# tx35.net
KiCad netlist of a schematic drawn in EAGLE
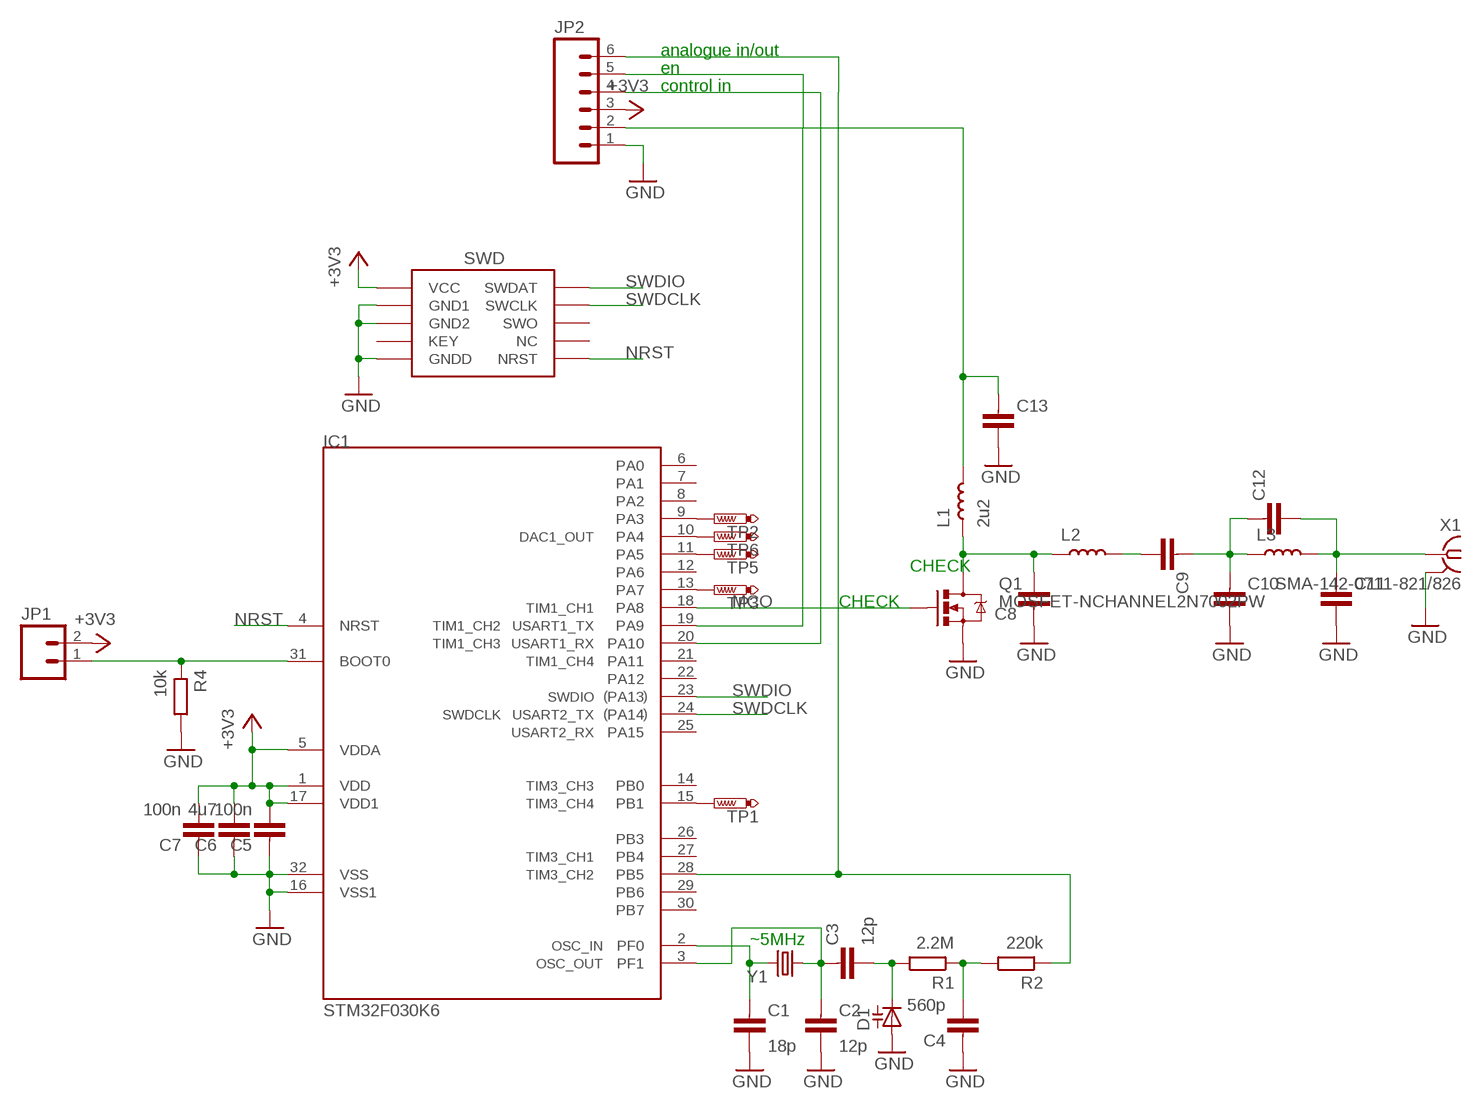
[diagram p0: schematic, sheet 1]

(export (version "E")
  (design (tool "Eeschema 10.0.6"))
  (components
    (comp (ref "C1")
      (value "18p")
      (footprint "eagle-import:C0603-N")
      (libsource (lib "eagle-import") (part "CAPACITOR0603-N"))
    )
    (comp (ref "C2")
      (value "12p")
      (footprint "eagle-import:C0603-N")
      (libsource (lib "eagle-import") (part "CAPACITOR0603-N"))
    )
    (comp (ref "C3")
      (value "12p")
      (footprint "eagle-import:C0603-N")
      (libsource (lib "eagle-import") (part "CAPACITOR0603-N"))
    )
    (comp (ref "C4")
      (value "560p")
      (footprint "eagle-import:C0603-N")
      (libsource (lib "eagle-import") (part "CAPACITOR0603-N"))
    )
    (comp (ref "C5")
      (value "100n")
      (footprint "eagle-import:C0603-N")
      (libsource (lib "eagle-import") (part "CAPACITOR0603-N"))
    )
    (comp (ref "C6")
      (value "4u7")
      (footprint "eagle-import:C0603-N")
      (libsource (lib "eagle-import") (part "CAPACITOR0603-N"))
    )
    (comp (ref "C7")
      (value "100n")
      (footprint "eagle-import:C0603-N")
      (libsource (lib "eagle-import") (part "CAPACITOR0603-N"))
    )
    (comp (ref "C8")
      (value "CAPACITOR0603-N")
      (footprint "eagle-import:C0603-N")
      (libsource (lib "eagle-import") (part "CAPACITOR0603-N"))
    )
    (comp (ref "C9")
      (value "CAPACITOR0603-N")
      (footprint "eagle-import:C0603-N")
      (libsource (lib "eagle-import") (part "CAPACITOR0603-N"))
    )
    (comp (ref "C10")
      (value "CAPACITOR0603-N")
      (footprint "eagle-import:C0603-N")
      (libsource (lib "eagle-import") (part "CAPACITOR0603-N"))
    )
    (comp (ref "C11")
      (value "CAPACITOR0603-N")
      (footprint "eagle-import:C0603-N")
      (libsource (lib "eagle-import") (part "CAPACITOR0603-N"))
    )
    (comp (ref "C12")
      (value "CAPACITOR0603-N")
      (footprint "eagle-import:C0603-N")
      (libsource (lib "eagle-import") (part "CAPACITOR0603-N"))
    )
    (comp (ref "C13")
      (value "CAPACITOR0805-N")
      (footprint "eagle-import:C0805-N")
      (libsource (lib "eagle-import") (part "CAPACITOR0805-N"))
    )
    (comp (ref "D1")
      (value "DIODE_CAPACITANCE-SOD523")
      (footprint "eagle-import:SOD523")
      (libsource (lib "eagle-import") (part "DIODE_CAPACITANCE-SOD523"))
    )
    (comp (ref "IC1")
      (value "STM32F030K6")
      (footprint "eagle-import:TQFP32-08")
      (libsource (lib "eagle-import") (part "STM32F0-32"))
    )
    (comp (ref "J1")
      (value "SWD_SHROUD")
      (footprint "eagle-import:SWD_PTH_SHROUD")
      (libsource (lib "eagle-import") (part "SWD_SHROUD"))
    )
    (comp (ref "JP1")
      (value "M02PTH")
      (footprint "eagle-import:1X02")
      (libsource (lib "eagle-import") (part "M02PTH"))
    )
    (comp (ref "JP2")
      (value "M06SILK_FEMALE_PTH")
      (footprint "eagle-import:1X06")
      (libsource (lib "eagle-import") (part "M06SILK_FEMALE_PTH"))
    )
    (comp (ref "L1")
      (value "2u2")
      (footprint "eagle-import:L0603-N")
      (libsource (lib "eagle-import") (part "INDUCTOR0603-N"))
    )
    (comp (ref "L2")
      (value "INDUCTOR0603-N")
      (footprint "eagle-import:L0603-N")
      (libsource (lib "eagle-import") (part "INDUCTOR0603-N"))
    )
    (comp (ref "L3")
      (value "INDUCTOR0603-N")
      (footprint "eagle-import:L0603-N")
      (libsource (lib "eagle-import") (part "INDUCTOR0603-N"))
    )
    (comp (ref "Q1")
      (value "MOSFET-NCHANNEL2N7002PW")
      (footprint "eagle-import:SOT323")
      (libsource (lib "eagle-import") (part "MOSFET-NCHANNEL2N7002PW"))
    )
    (comp (ref "R1")
      (value "2.2M")
      (footprint "eagle-import:R0603-N")
      (libsource (lib "eagle-import") (part "RESISTOR0603-N"))
    )
    (comp (ref "R2")
      (value "220k")
      (footprint "eagle-import:R0603-N")
      (libsource (lib "eagle-import") (part "RESISTOR0603-N"))
    )
    (comp (ref "R4")
      (value "10k")
      (footprint "eagle-import:R0603-N")
      (libsource (lib "eagle-import") (part "RESISTOR0603-N"))
    )
    (comp (ref "TP1")
      (value "PTR1TP11R")
      (footprint "eagle-import:TP11R")
      (libsource (lib "eagle-import") (part "PTR1TP11R"))
    )
    (comp (ref "TP2")
      (value "PTR1TP11R")
      (footprint "eagle-import:TP11R")
      (libsource (lib "eagle-import") (part "PTR1TP11R"))
    )
    (comp (ref "TP3")
      (value "PTR1TP11R")
      (footprint "eagle-import:TP11R")
      (libsource (lib "eagle-import") (part "PTR1TP11R"))
    )
    (comp (ref "TP5")
      (value "PTR1TP11R")
      (footprint "eagle-import:TP11R")
      (libsource (lib "eagle-import") (part "PTR1TP11R"))
    )
    (comp (ref "TP6")
      (value "PTR1TP11R")
      (footprint "eagle-import:TP11R")
      (libsource (lib "eagle-import") (part "PTR1TP11R"))
    )
    (comp (ref "X1")
      (value "SMA-142-0711-821/826")
      (footprint "eagle-import:J502-ND-142-0711-821_826")
      (fields (field (name "MF") "JOHNSON COMPONENTS") (field (name "MPN") "142-0711-821"))
      (libsource (lib "eagle-import") (part "SMA-142-0711-821/826"))
    )
    (comp (ref "Y1")
      (value "CRYSTALHC49UV")
      (footprint "eagle-import:HC49U-V")
      (libsource (lib "eagle-import") (part "CRYSTALHC49UV"))
    )
  )
  (nets
    (net (code "1") (name "+3V3") (class "Default")
      (node (ref "C5") (pin "2") (pinfunction "2_2") (pintype "passive"))
      (node (ref "C6") (pin "2") (pinfunction "2_2") (pintype "passive"))
      (node (ref "C7") (pin "2") (pinfunction "2_2") (pintype "passive"))
      (node (ref "IC1") (pin "1") (pinfunction "VDD_1") (pintype "power_in"))
      (node (ref "IC1") (pin "17") (pinfunction "VDD1_17") (pintype "power_in"))
      (node (ref "IC1") (pin "5") (pinfunction "VDDA_5") (pintype "power_in"))
      (node (ref "J1") (pin "1") (pinfunction "VCC_1") (pintype "power_in"))
      (node (ref "JP1") (pin "2") (pinfunction "2_2") (pintype "passive"))
      (node (ref "JP2") (pin "3") (pinfunction "3_3") (pintype "passive"))
    )
    (net (code "2") (name "/MCO") (class "Default")
      (node (ref "IC1") (pin "18") (pinfunction "PA8_18") (pintype "bidirectional"))
      (node (ref "Q1") (pin "1") (pinfunction "G_1") (pintype "passive"))
    )
    (net (code "3") (name "/NRST") (class "Default")
      (node (ref "IC1") (pin "4") (pinfunction "NRST_4") (pintype "input"))
      (node (ref "J1") (pin "10") (pinfunction "NRST_10") (pintype "bidirectional"))
    )
    (net (code "4") (name "/SWDCLK") (class "Default")
      (node (ref "IC1") (pin "24") (pinfunction "PA14_24") (pintype "bidirectional"))
      (node (ref "J1") (pin "4") (pinfunction "SWCLK_4") (pintype "bidirectional"))
    )
    (net (code "5") (name "/SWDIO") (class "Default")
      (node (ref "IC1") (pin "23") (pinfunction "PA13_23") (pintype "bidirectional"))
      (node (ref "J1") (pin "2") (pinfunction "SWDAT_2") (pintype "bidirectional"))
    )
    (net (code "6") (name "GND") (class "Default")
      (node (ref "C1") (pin "2") (pinfunction "2_2") (pintype "passive"))
      (node (ref "C10") (pin "2") (pinfunction "2_2") (pintype "passive"))
      (node (ref "C11") (pin "2") (pinfunction "2_2") (pintype "passive"))
      (node (ref "C13") (pin "2") (pinfunction "2_2") (pintype "passive"))
      (node (ref "C2") (pin "2") (pinfunction "2_2") (pintype "passive"))
      (node (ref "C4") (pin "1") (pinfunction "1_1") (pintype "passive"))
      (node (ref "C5") (pin "1") (pinfunction "1_1") (pintype "passive"))
      (node (ref "C6") (pin "1") (pinfunction "1_1") (pintype "passive"))
      (node (ref "C7") (pin "1") (pinfunction "1_1") (pintype "passive"))
      (node (ref "C8") (pin "1") (pinfunction "1_1") (pintype "passive"))
      (node (ref "D1") (pin "A") (pinfunction "A_A") (pintype "passive"))
      (node (ref "IC1") (pin "16") (pinfunction "VSS1_16") (pintype "power_in"))
      (node (ref "IC1") (pin "32") (pinfunction "VSS_32") (pintype "power_in"))
      (node (ref "J1") (pin "3") (pinfunction "GND1_3") (pintype "power_in"))
      (node (ref "J1") (pin "5") (pinfunction "GND2_5") (pintype "power_in"))
      (node (ref "J1") (pin "9") (pinfunction "GNDD_9") (pintype "power_in"))
      (node (ref "JP2") (pin "1") (pinfunction "1_1") (pintype "passive"))
      (node (ref "Q1") (pin "2") (pinfunction "S_2") (pintype "passive"))
      (node (ref "R4") (pin "2") (pinfunction "P$2_2") (pintype "passive"))
      (node (ref "X1") (pin "G@1") (pinfunction "2_G@1") (pintype "passive"))
      (node (ref "X1") (pin "G@2") (pinfunction "2_G@2") (pintype "passive"))
      (node (ref "X1") (pin "G@3") (pinfunction "2_G@3") (pintype "passive"))
      (node (ref "X1") (pin "G@4") (pinfunction "2_G@4") (pintype "passive"))
    )
    (net (code "7") (name "Net-(IC1-BOOT0)") (class "Default")
      (node (ref "IC1") (pin "31") (pinfunction "BOOT0_31") (pintype "input"))
      (node (ref "JP1") (pin "1") (pinfunction "1_1") (pintype "passive"))
      (node (ref "R4") (pin "1") (pinfunction "P$1_1") (pintype "passive"))
    )
    (net (code "8") (name "Net-(IC1-PA3)") (class "Default")
      (node (ref "IC1") (pin "9") (pinfunction "PA3_9") (pintype "bidirectional"))
      (node (ref "TP2") (pin "TP") (pinfunction "TP_TP") (pintype "input"))
    )
    (net (code "9") (name "Net-(IC1-PA4)") (class "Default")
      (node (ref "IC1") (pin "10") (pinfunction "PA4_10") (pintype "bidirectional"))
      (node (ref "TP6") (pin "TP") (pinfunction "TP_TP") (pintype "input"))
    )
    (net (code "10") (name "Net-(IC1-PA5)") (class "Default")
      (node (ref "IC1") (pin "11") (pinfunction "PA5_11") (pintype "bidirectional"))
      (node (ref "TP5") (pin "TP") (pinfunction "TP_TP") (pintype "input"))
    )
    (net (code "11") (name "Net-(IC1-PA7)") (class "Default")
      (node (ref "IC1") (pin "13") (pinfunction "PA7_13") (pintype "bidirectional"))
      (node (ref "TP3") (pin "TP") (pinfunction "TP_TP") (pintype "input"))
    )
    (net (code "12") (name "Net-(IC1-PA9)") (class "Default")
      (node (ref "IC1") (pin "19") (pinfunction "PA9_19") (pintype "bidirectional"))
      (node (ref "JP2") (pin "5") (pinfunction "5_5") (pintype "passive"))
    )
    (net (code "13") (name "Net-(IC1-PA10)") (class "Default")
      (node (ref "IC1") (pin "20") (pinfunction "PA10_20") (pintype "bidirectional"))
      (node (ref "JP2") (pin "4") (pinfunction "4_4") (pintype "passive"))
    )
    (net (code "14") (name "Net-(IC1-PB1)") (class "Default")
      (node (ref "IC1") (pin "15") (pinfunction "PB1_15") (pintype "bidirectional"))
      (node (ref "TP1") (pin "TP") (pinfunction "TP_TP") (pintype "input"))
    )
    (net (code "15") (name "Net-(IC1-PB5)") (class "Default")
      (node (ref "IC1") (pin "28") (pinfunction "PB5_28") (pintype "bidirectional"))
      (node (ref "JP2") (pin "6") (pinfunction "6_6") (pintype "passive"))
      (node (ref "R2") (pin "1") (pinfunction "P$1_1") (pintype "passive"))
    )
    (net (code "16") (name "Net-(IC1-PF0)") (class "Default")
      (node (ref "C1") (pin "1") (pinfunction "1_1") (pintype "passive"))
      (node (ref "IC1") (pin "2") (pinfunction "PF0_2") (pintype "bidirectional"))
      (node (ref "Y1") (pin "2") (pinfunction "2_2") (pintype "passive"))
    )
    (net (code "17") (name "Net-(IC1-PF1)") (class "Default")
      (node (ref "C2") (pin "1") (pinfunction "1_1") (pintype "passive"))
      (node (ref "C3") (pin "1") (pinfunction "1_1") (pintype "passive"))
      (node (ref "IC1") (pin "3") (pinfunction "PF1_3") (pintype "bidirectional"))
      (node (ref "Y1") (pin "1") (pinfunction "1_1") (pintype "passive"))
    )
    (net (code "18") (name "Net-(L1-P$1)") (class "Default")
      (node (ref "C8") (pin "2") (pinfunction "2_2") (pintype "passive"))
      (node (ref "L1") (pin "1") (pinfunction "P$1_1") (pintype "passive"))
      (node (ref "L2") (pin "1") (pinfunction "P$1_1") (pintype "passive"))
      (node (ref "Q1") (pin "3") (pinfunction "D_3") (pintype "passive"))
    )
    (net (code "19") (name "Net-(L1-P$2)") (class "Default")
      (node (ref "C13") (pin "1") (pinfunction "1_1") (pintype "passive"))
      (node (ref "JP2") (pin "2") (pinfunction "2_2") (pintype "passive"))
      (node (ref "L1") (pin "2") (pinfunction "P$2_2") (pintype "passive"))
    )
    (net (code "20") (name "Net-(L2-P$2)") (class "Default")
      (node (ref "C9") (pin "2") (pinfunction "2_2") (pintype "passive"))
      (node (ref "L2") (pin "2") (pinfunction "P$2_2") (pintype "passive"))
    )
    (net (code "21") (name "Net-(L3-P$1)") (class "Default")
      (node (ref "C10") (pin "1") (pinfunction "1_1") (pintype "passive"))
      (node (ref "C12") (pin "1") (pinfunction "1_1") (pintype "passive"))
      (node (ref "C9") (pin "1") (pinfunction "1_1") (pintype "passive"))
      (node (ref "L3") (pin "1") (pinfunction "P$1_1") (pintype "passive"))
    )
    (net (code "22") (name "Net-(L3-P$2)") (class "Default")
      (node (ref "C11") (pin "1") (pinfunction "1_1") (pintype "passive"))
      (node (ref "C12") (pin "2") (pinfunction "2_2") (pintype "passive"))
      (node (ref "L3") (pin "2") (pinfunction "P$2_2") (pintype "passive"))
      (node (ref "X1") (pin "1") (pinfunction "1_1") (pintype "passive"))
    )
    (net (code "23") (name "Net-(R1-P$1)") (class "Default")
      (node (ref "C4") (pin "2") (pinfunction "2_2") (pintype "passive"))
      (node (ref "R1") (pin "1") (pinfunction "P$1_1") (pintype "passive"))
      (node (ref "R2") (pin "2") (pinfunction "P$2_2") (pintype "passive"))
    )
    (net (code "24") (name "Net-(R1-P$2)") (class "Default")
      (node (ref "C3") (pin "2") (pinfunction "2_2") (pintype "passive"))
      (node (ref "D1") (pin "C") (pinfunction "C_C") (pintype "passive"))
      (node (ref "R1") (pin "2") (pinfunction "P$2_2") (pintype "passive"))
    )
    (net (code "25") (name "unconnected-(IC1-PA0-Pad6)") (class "Default")
      (node (ref "IC1") (pin "6") (pinfunction "PA0_6") (pintype "bidirectional"))
    )
    (net (code "26") (name "unconnected-(IC1-PA1-Pad7)") (class "Default")
      (node (ref "IC1") (pin "7") (pinfunction "PA1_7") (pintype "bidirectional"))
    )
    (net (code "27") (name "unconnected-(IC1-PA2-Pad8)") (class "Default")
      (node (ref "IC1") (pin "8") (pinfunction "PA2_8") (pintype "bidirectional"))
    )
    (net (code "28") (name "unconnected-(IC1-PA6-Pad12)") (class "Default")
      (node (ref "IC1") (pin "12") (pinfunction "PA6_12") (pintype "bidirectional"))
    )
    (net (code "29") (name "unconnected-(IC1-PA11-Pad21)") (class "Default")
      (node (ref "IC1") (pin "21") (pinfunction "PA11_21") (pintype "bidirectional"))
    )
    (net (code "30") (name "unconnected-(IC1-PA12-Pad22)") (class "Default")
      (node (ref "IC1") (pin "22") (pinfunction "PA12_22") (pintype "bidirectional"))
    )
    (net (code "31") (name "unconnected-(IC1-PA15-Pad25)") (class "Default")
      (node (ref "IC1") (pin "25") (pinfunction "PA15_25") (pintype "bidirectional"))
    )
    (net (code "32") (name "unconnected-(IC1-PB0-Pad14)") (class "Default")
      (node (ref "IC1") (pin "14") (pinfunction "PB0_14") (pintype "bidirectional"))
    )
    (net (code "33") (name "unconnected-(IC1-PB3-Pad26)") (class "Default")
      (node (ref "IC1") (pin "26") (pinfunction "PB3_26") (pintype "bidirectional"))
    )
    (net (code "34") (name "unconnected-(IC1-PB4-Pad27)") (class "Default")
      (node (ref "IC1") (pin "27") (pinfunction "PB4_27") (pintype "bidirectional"))
    )
    (net (code "35") (name "unconnected-(IC1-PB6-Pad29)") (class "Default")
      (node (ref "IC1") (pin "29") (pinfunction "PB6_29") (pintype "bidirectional"))
    )
    (net (code "36") (name "unconnected-(IC1-PB7-Pad30)") (class "Default")
      (node (ref "IC1") (pin "30") (pinfunction "PB7_30") (pintype "bidirectional"))
    )
    (net (code "37") (name "unconnected-(J1-KEY-Pad7)") (class "Default")
      (node (ref "J1") (pin "7") (pinfunction "KEY_7") (pintype "bidirectional"))
    )
    (net (code "38") (name "unconnected-(J1-NC-Pad8)") (class "Default")
      (node (ref "J1") (pin "8") (pinfunction "NC_8") (pintype "no_connect"))
    )
    (net (code "39") (name "unconnected-(J1-SWO-Pad6)") (class "Default")
      (node (ref "J1") (pin "6") (pinfunction "SWO_6") (pintype "bidirectional"))
    )
  )
)
